# fablab-example.net
KiCad netlist of a schematic drawn in EAGLE
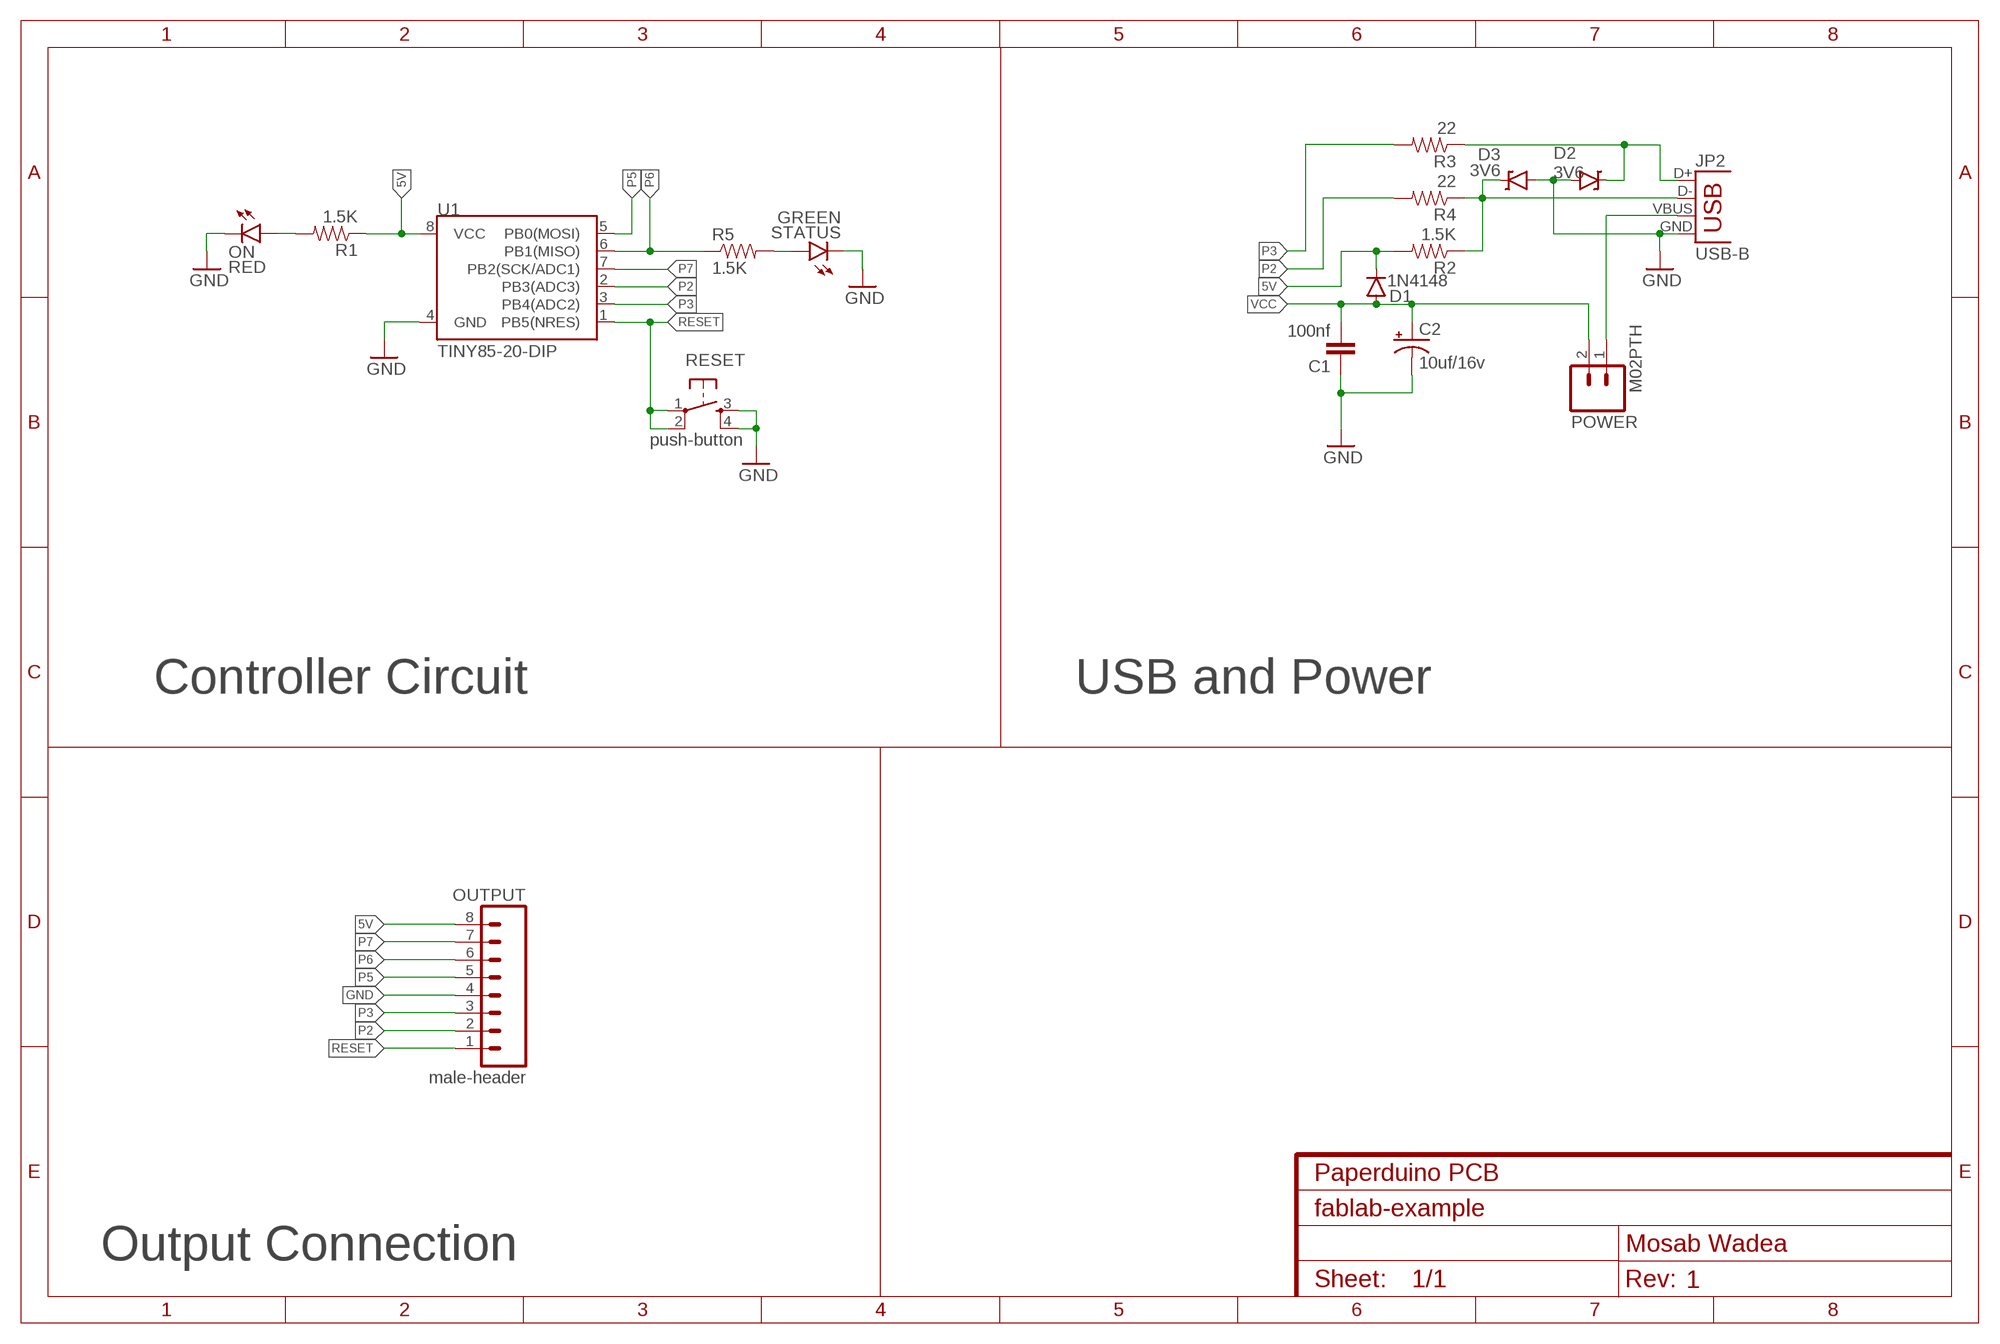
[diagram p0: schematic, sheet 1]

(export (version "E")
  (design (tool "Eeschema 10.0.6"))
  (components
    (comp (ref "C1")
      (value "100nf")
      (footprint "eagle-import:CAP-PTH-SMALL")
      (libsource (lib "eagle-import") (part "CAPPTH"))
    )
    (comp (ref "C2")
      (value "10uf/16v")
      (footprint "eagle-import:CPOL-RADIAL-10UF-25V")
      (libsource (lib "eagle-import") (part "CAP_POLPTH2"))
    )
    (comp (ref "D1")
      (value "1N4148")
      (footprint "eagle-import:DIODE-1N4148")
      (libsource (lib "eagle-import") (part "DIODE1N4148"))
    )
    (comp (ref "D2")
      (value "3V6")
      (footprint "eagle-import:DIODE-ZENER")
      (libsource (lib "eagle-import") (part "DIODE-ZENERPTH"))
    )
    (comp (ref "D3")
      (value "3V6")
      (footprint "eagle-import:DIODE-ZENER")
      (libsource (lib "eagle-import") (part "DIODE-ZENERPTH"))
    )
    (comp (ref "JP2")
      (value "USB-B")
      (footprint "eagle-import:USB-B-PTH")
      (libsource (lib "eagle-import") (part "USBPTH"))
    )
    (comp (ref "ON")
      (value "RED")
      (footprint "eagle-import:LED3MM")
      (libsource (lib "eagle-import") (part "LED3MM"))
    )
    (comp (ref "OUTPUT")
      (value "male-header")
      (footprint "eagle-import:1X08_ROUND")
      (libsource (lib "eagle-import") (part "M08"))
    )
    (comp (ref "POWER")
      (value "M02PTH")
      (footprint "eagle-import:1X02")
      (libsource (lib "eagle-import") (part "M02PTH"))
    )
    (comp (ref "R1")
      (value "1.5K")
      (footprint "eagle-import:1206")
      (libsource (lib "eagle-import") (part "RESISTOR1206"))
    )
    (comp (ref "R2")
      (value "1.5K")
      (footprint "eagle-import:1206")
      (libsource (lib "eagle-import") (part "RESISTOR1206"))
    )
    (comp (ref "R3")
      (value "22")
      (footprint "eagle-import:1206")
      (libsource (lib "eagle-import") (part "RESISTOR1206"))
    )
    (comp (ref "R4")
      (value "22")
      (footprint "eagle-import:1206")
      (libsource (lib "eagle-import") (part "RESISTOR1206"))
    )
    (comp (ref "R5")
      (value "1.5K")
      (footprint "eagle-import:1206")
      (libsource (lib "eagle-import") (part "RESISTOR1206"))
    )
    (comp (ref "RESET")
      (value "push-button")
      (footprint "eagle-import:TACTILE-PTH")
      (libsource (lib "eagle-import") (part "TAC_SWITCHPTH"))
    )
    (comp (ref "STATUS")
      (value "GREEN")
      (footprint "eagle-import:LED3MM")
      (libsource (lib "eagle-import") (part "LED3MM"))
    )
    (comp (ref "U1")
      (value "TINY85-20-DIP")
      (footprint "eagle-import:DIP08")
      (libsource (lib "eagle-import") (part "ATTINY45TINY85-20-DIP"))
    )
  )
  (nets
    (net (code "1") (name "5V") (class "Default")
      (node (ref "D1") (pin "C") (pinfunction "C_C") (pintype "passive"))
      (node (ref "OUTPUT") (pin "8") (pinfunction "8_8") (pintype "passive"))
      (node (ref "R1") (pin "1") (pinfunction "1_1") (pintype "passive"))
      (node (ref "R2") (pin "2") (pinfunction "2_2") (pintype "passive"))
      (node (ref "U1") (pin "8") (pinfunction "VCC_8") (pintype "bidirectional"))
    )
    (net (code "2") (name "GND") (class "Default")
      (node (ref "C1") (pin "1") (pinfunction "1_1") (pintype "passive"))
      (node (ref "C2") (pin "2") (pinfunction "-_2") (pintype "passive"))
      (node (ref "D2") (pin "P$2") (pinfunction "A_P$2") (pintype "passive"))
      (node (ref "D3") (pin "P$2") (pinfunction "A_P$2") (pintype "passive"))
      (node (ref "JP2") (pin "GND") (pinfunction "GND_GND") (pintype "bidirectional"))
      (node (ref "ON") (pin "K") (pinfunction "C_K") (pintype "passive"))
      (node (ref "OUTPUT") (pin "4") (pinfunction "4_4") (pintype "passive"))
      (node (ref "RESET") (pin "3") (pinfunction "3_3") (pintype "passive"))
      (node (ref "RESET") (pin "4") (pinfunction "4_4") (pintype "passive"))
      (node (ref "STATUS") (pin "K") (pinfunction "C_K") (pintype "passive"))
      (node (ref "U1") (pin "4") (pinfunction "GND_4") (pintype "bidirectional"))
    )
    (net (code "3") (name "Net-(D2-C)") (class "Default")
      (node (ref "D2") (pin "P$1") (pinfunction "C_P$1") (pintype "passive"))
      (node (ref "JP2") (pin "D+") (pinfunction "D+_D+") (pintype "bidirectional"))
      (node (ref "R3") (pin "1") (pinfunction "1_1") (pintype "passive"))
    )
    (net (code "4") (name "Net-(D3-C)") (class "Default")
      (node (ref "D3") (pin "P$1") (pinfunction "C_P$1") (pintype "passive"))
      (node (ref "JP2") (pin "D-") (pinfunction "D-_D-") (pintype "bidirectional"))
      (node (ref "R2") (pin "1") (pinfunction "1_1") (pintype "passive"))
      (node (ref "R4") (pin "1") (pinfunction "1_1") (pintype "passive"))
    )
    (net (code "5") (name "Net-(JP2-PadVBUS)") (class "Default")
      (node (ref "JP2") (pin "VBUS") (pinfunction "VBUS_VBUS") (pintype "bidirectional"))
      (node (ref "POWER") (pin "1") (pinfunction "1_1") (pintype "passive"))
    )
    (net (code "6") (name "Net-(ON-PadA)") (class "Default")
      (node (ref "ON") (pin "A") (pinfunction "A_A") (pintype "passive"))
      (node (ref "R1") (pin "2") (pinfunction "2_2") (pintype "passive"))
    )
    (net (code "7") (name "Net-(R5-Pad2)") (class "Default")
      (node (ref "R5") (pin "2") (pinfunction "2_2") (pintype "passive"))
      (node (ref "STATUS") (pin "A") (pinfunction "A_A") (pintype "passive"))
    )
    (net (code "8") (name "P2") (class "Default")
      (node (ref "OUTPUT") (pin "2") (pinfunction "2_2") (pintype "passive"))
      (node (ref "R4") (pin "2") (pinfunction "2_2") (pintype "passive"))
      (node (ref "U1") (pin "2") (pinfunction "PB3(ADC3)_2") (pintype "bidirectional"))
    )
    (net (code "9") (name "P3") (class "Default")
      (node (ref "OUTPUT") (pin "3") (pinfunction "3_3") (pintype "passive"))
      (node (ref "R3") (pin "2") (pinfunction "2_2") (pintype "passive"))
      (node (ref "U1") (pin "3") (pinfunction "PB4(ADC2)_3") (pintype "bidirectional"))
    )
    (net (code "10") (name "P5") (class "Default")
      (node (ref "OUTPUT") (pin "5") (pinfunction "5_5") (pintype "passive"))
      (node (ref "U1") (pin "5") (pinfunction "PB0(MOSI)_5") (pintype "bidirectional"))
    )
    (net (code "11") (name "P6") (class "Default")
      (node (ref "OUTPUT") (pin "6") (pinfunction "6_6") (pintype "passive"))
      (node (ref "R5") (pin "1") (pinfunction "1_1") (pintype "passive"))
      (node (ref "U1") (pin "6") (pinfunction "PB1(MISO)_6") (pintype "bidirectional"))
    )
    (net (code "12") (name "P7") (class "Default")
      (node (ref "OUTPUT") (pin "7") (pinfunction "7_7") (pintype "passive"))
      (node (ref "U1") (pin "7") (pinfunction "PB2(SCK/ADC1)_7") (pintype "bidirectional"))
    )
    (net (code "13") (name "RESET") (class "Default")
      (node (ref "OUTPUT") (pin "1") (pinfunction "1_1") (pintype "passive"))
      (node (ref "RESET") (pin "1") (pinfunction "1_1") (pintype "passive"))
      (node (ref "RESET") (pin "2") (pinfunction "2_2") (pintype "passive"))
      (node (ref "U1") (pin "1") (pinfunction "PB5(NRES)_1") (pintype "bidirectional"))
    )
    (net (code "14") (name "VCC") (class "Default")
      (node (ref "C1") (pin "2") (pinfunction "2_2") (pintype "passive"))
      (node (ref "C2") (pin "1") (pinfunction "+_1") (pintype "passive"))
      (node (ref "D1") (pin "A") (pinfunction "A_A") (pintype "passive"))
      (node (ref "POWER") (pin "2") (pinfunction "2_2") (pintype "passive"))
    )
  )
)
